# PLL.net
KiCad netlist of a schematic drawn in Altium Designer
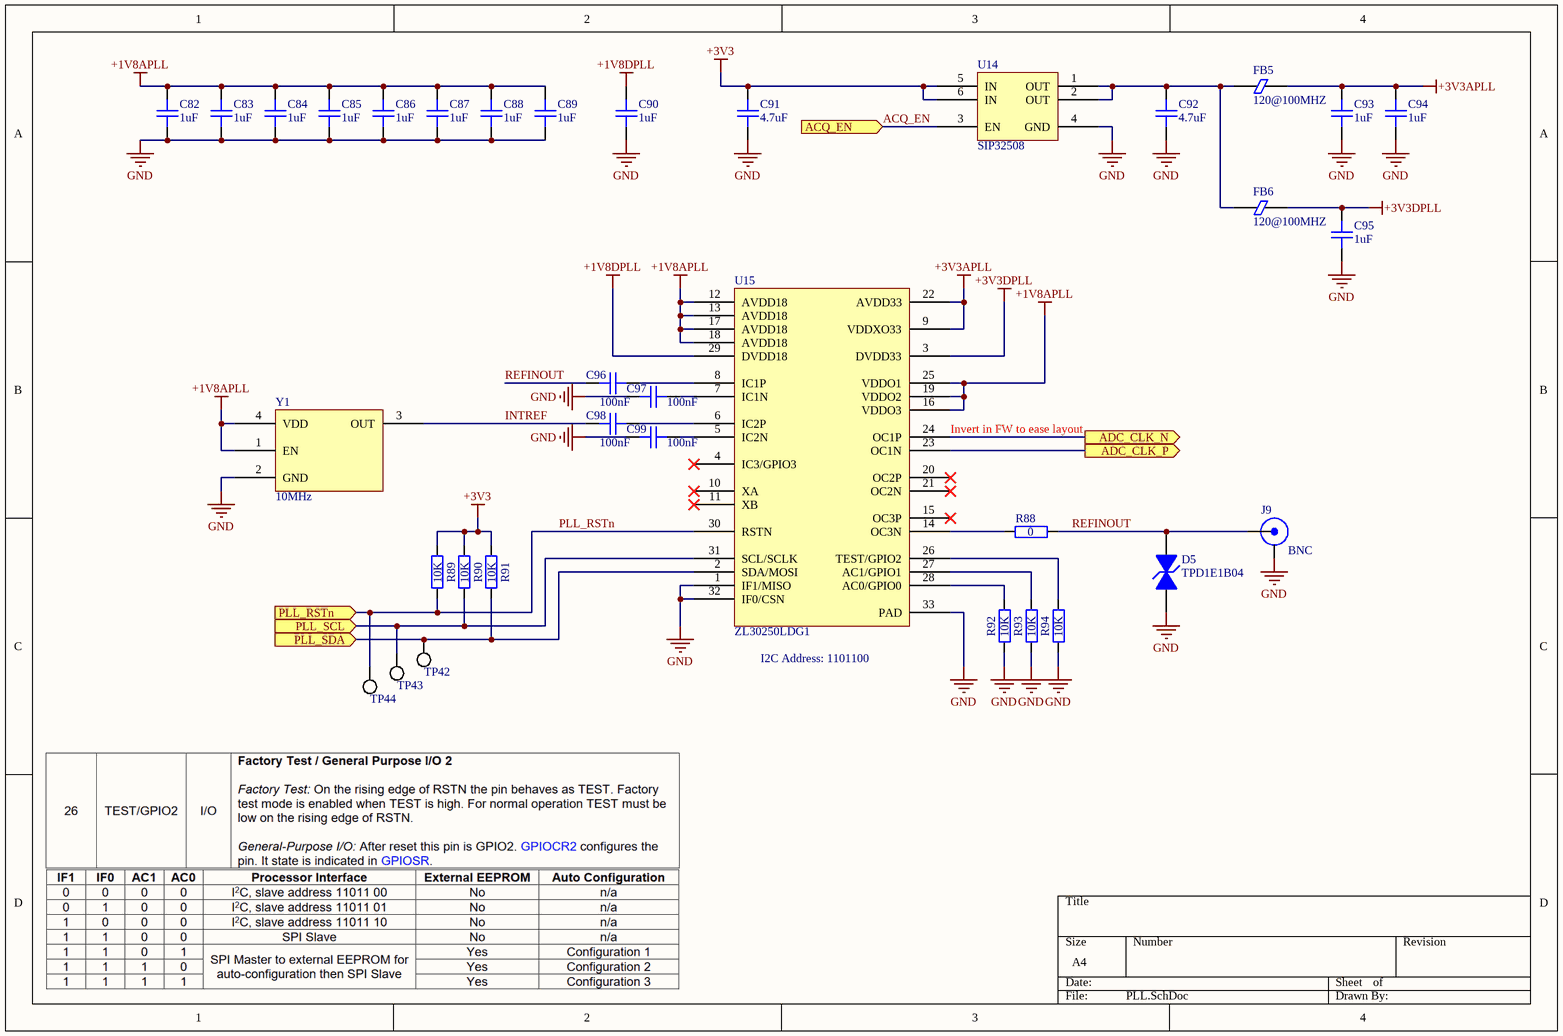
[diagram p0: PLL.SchDoc]

(export (version "E")
  (design (tool "Eeschema 10.0.6"))
  (components
    (comp (ref "C82")
      (value "1uF")
      (footprint "GEN_C_0402")
      (libsource (lib "DSO") (part "CAP 1uF 25V X5R 0402"))
    )
    (comp (ref "C83")
      (value "1uF")
      (footprint "GEN_C_0402")
      (libsource (lib "DSO") (part "CAP 1uF 25V X5R 0402"))
    )
    (comp (ref "C84")
      (value "1uF")
      (footprint "GEN_C_0402")
      (libsource (lib "DSO") (part "CAP 1uF 25V X5R 0402"))
    )
    (comp (ref "C85")
      (value "1uF")
      (footprint "GEN_C_0402")
      (libsource (lib "DSO") (part "CAP 1uF 25V X5R 0402"))
    )
    (comp (ref "C86")
      (value "1uF")
      (footprint "GEN_C_0402")
      (libsource (lib "DSO") (part "CAP 1uF 25V X5R 0402"))
    )
    (comp (ref "C87")
      (value "1uF")
      (footprint "GEN_C_0402")
      (libsource (lib "DSO") (part "CAP 1uF 25V X5R 0402"))
    )
    (comp (ref "C88")
      (value "1uF")
      (footprint "GEN_C_0402")
      (libsource (lib "DSO") (part "CAP 1uF 25V X5R 0402"))
    )
    (comp (ref "C89")
      (value "1uF")
      (footprint "GEN_C_0402")
      (libsource (lib "DSO") (part "CAP 1uF 25V X5R 0402"))
    )
    (comp (ref "C90")
      (value "1uF")
      (footprint "GEN_C_0402")
      (libsource (lib "DSO") (part "CAP 1uF 25V X5R 0402"))
    )
    (comp (ref "C91")
      (value "4.7uF")
      (footprint "GEN_C_0402")
      (libsource (lib "DSO") (part "CAP 4.7uF 6.3V X5R 0402"))
    )
    (comp (ref "C92")
      (value "4.7uF")
      (footprint "GEN_C_0402")
      (libsource (lib "DSO") (part "CAP 4.7uF 6.3V X5R 0402"))
    )
    (comp (ref "C93")
      (value "1uF")
      (footprint "GEN_C_0402")
      (libsource (lib "DSO") (part "CAP 1uF 25V X5R 0402"))
    )
    (comp (ref "C94")
      (value "1uF")
      (footprint "GEN_C_0402")
      (libsource (lib "DSO") (part "CAP 1uF 25V X5R 0402"))
    )
    (comp (ref "C95")
      (value "1uF")
      (footprint "GEN_C_0402")
      (libsource (lib "DSO") (part "CAP 1uF 25V X5R 0402"))
    )
    (comp (ref "C96")
      (value "100nF")
      (footprint "GEN_C_0402")
      (libsource (lib "DSO") (part "CAP 100nF 16V X7R 0402"))
    )
    (comp (ref "C97")
      (value "100nF")
      (footprint "GEN_C_0402")
      (libsource (lib "DSO") (part "CAP 100nF 16V X7R 0402"))
    )
    (comp (ref "C98")
      (value "100nF")
      (footprint "GEN_C_0402")
      (libsource (lib "DSO") (part "CAP 100nF 16V X7R 0402"))
    )
    (comp (ref "C99")
      (value "100nF")
      (footprint "GEN_C_0402")
      (libsource (lib "DSO") (part "CAP 100nF 16V X7R 0402"))
    )
    (comp (ref "D5")
      (value "TPD1E1B04")
      (footprint "TI_X1SON_DPY0002A")
      (libsource (lib "DSO") (part "TVS TPD1E1B04"))
    )
    (comp (ref "FB5")
      (value "120@100MHZ")
      (footprint "GEN_R_0402")
      (libsource (lib "DSO") (part "FERRITE BEAD 120 OHM 0402"))
    )
    (comp (ref "FB6")
      (value "120@100MHZ")
      (footprint "GEN_R_0402")
      (libsource (lib "DSO") (part "FERRITE BEAD 120 OHM 0402"))
    )
    (comp (ref "J9") (value "BNC") (footprint "MOL_0731000105") (libsource (lib "DSO") (part "BNC JACK R/A")))
    (comp (ref "R88")
      (value "0")
      (footprint "GEN_R_0402")
      (libsource (lib "DSO") (part "RES 0 OHM 1/16W 0402"))
    )
    (comp (ref "R89")
      (value "10K")
      (footprint "GEN_R_0402")
      (fields (field (name "TOLERANCE") "1%"))
      (libsource (lib "DSO") (part "RES 10K OHM 1% 1/10W 0402"))
    )
    (comp (ref "R90")
      (value "10K")
      (footprint "GEN_R_0402")
      (fields (field (name "TOLERANCE") "1%"))
      (libsource (lib "DSO") (part "RES 10K OHM 1% 1/10W 0402"))
    )
    (comp (ref "R91")
      (value "10K")
      (footprint "GEN_R_0402")
      (fields (field (name "TOLERANCE") "1%"))
      (libsource (lib "DSO") (part "RES 10K OHM 1% 1/10W 0402"))
    )
    (comp (ref "R92")
      (value "10K")
      (footprint "GEN_R_0402")
      (fields (field (name "TOLERANCE") "1%"))
      (libsource (lib "") (part "RES 10K OHM 1% 1/10W 0402_1"))
    )
    (comp (ref "R93")
      (value "10K")
      (footprint "GEN_R_0402")
      (fields (field (name "TOLERANCE") "1%"))
      (libsource (lib "") (part "RES 10K OHM 1% 1/10W 0402_1"))
    )
    (comp (ref "R94")
      (value "10K")
      (footprint "GEN_R_0402")
      (fields (field (name "TOLERANCE") "1%"))
      (libsource (lib "") (part "RES 10K OHM 1% 1/10W 0402_1"))
    )
    (comp (ref "TP42") (value "PCB") (footprint "GEN_TP_PCB") (libsource (lib "DSO") (part "TP PCB 1mm")))
    (comp (ref "TP43") (value "PCB") (footprint "GEN_TP_PCB") (libsource (lib "DSO") (part "TP PCB 1mm")))
    (comp (ref "TP44") (value "PCB") (footprint "GEN_TP_PCB") (libsource (lib "DSO") (part "TP PCB 1mm")))
    (comp (ref "U14")
      (value "SIP32508")
      (footprint "VISH_TSOT6")
      (libsource (lib "DSO") (part "IC SWITCH LOAD SIP32508"))
    )
    (comp (ref "U15")
      (value "ZL30250LDG1")
      (footprint "MC_QFN32_ZL30250")
      (libsource (lib "DSO") (part "IC CLK GEN ZL30250LDG1"))
    )
    (comp (ref "Y1")
      (value "10MHz")
      (footprint "ECS_TXO-3225")
      (libsource (lib "DSO") (part "OSC 10MHz ECS-TXO-3225MV"))
    )
  )
  (nets
    (net (code "1") (name "+1V8APLL") (class "Default")
      (node (ref "C82") (pin "1") (pinfunction "1_1") (pintype "passive"))
      (node (ref "C83") (pin "1") (pinfunction "1_1") (pintype "passive"))
      (node (ref "C84") (pin "1") (pinfunction "1_1") (pintype "passive"))
      (node (ref "C85") (pin "1") (pinfunction "1_1") (pintype "passive"))
      (node (ref "C86") (pin "1") (pinfunction "1_1") (pintype "passive"))
      (node (ref "C87") (pin "1") (pinfunction "1_1") (pintype "passive"))
      (node (ref "C88") (pin "1") (pinfunction "1_1") (pintype "passive"))
      (node (ref "C89") (pin "1") (pinfunction "1_1") (pintype "passive"))
      (node (ref "U15") (pin "12") (pinfunction "AVDD18_12") (pintype "passive"))
      (node (ref "U15") (pin "13") (pinfunction "AVDD18_13") (pintype "passive"))
      (node (ref "U15") (pin "16") (pinfunction "VDDO3_16") (pintype "passive"))
      (node (ref "U15") (pin "17") (pinfunction "AVDD18_17") (pintype "passive"))
      (node (ref "U15") (pin "18") (pinfunction "AVDD18_18") (pintype "passive"))
      (node (ref "U15") (pin "19") (pinfunction "VDDO2_19") (pintype "passive"))
      (node (ref "U15") (pin "25") (pinfunction "VDDO1_25") (pintype "passive"))
      (node (ref "Y1") (pin "1") (pinfunction "EN_1") (pintype "passive"))
      (node (ref "Y1") (pin "4") (pinfunction "VDD_4") (pintype "power_in"))
    )
    (net (code "2") (name "+1V8DPLL") (class "Default")
      (node (ref "C90") (pin "1") (pinfunction "1_1") (pintype "passive"))
      (node (ref "U15") (pin "29") (pinfunction "DVDD18_29") (pintype "passive"))
    )
    (net (code "3") (name "+3V3") (class "Default")
      (node (ref "C91") (pin "2") (pinfunction "2_2") (pintype "passive"))
      (node (ref "R89") (pin "2") (pinfunction "2_2") (pintype "passive"))
      (node (ref "R90") (pin "2") (pinfunction "2_2") (pintype "passive"))
      (node (ref "R91") (pin "2") (pinfunction "2_2") (pintype "passive"))
      (node (ref "U14") (pin "5") (pinfunction "IN_5") (pintype "passive"))
      (node (ref "U14") (pin "6") (pinfunction "IN_6") (pintype "passive"))
    )
    (net (code "4") (name "+3V3APLL") (class "Default")
      (node (ref "C93") (pin "1") (pinfunction "1_1") (pintype "passive"))
      (node (ref "C94") (pin "1") (pinfunction "1_1") (pintype "passive"))
      (node (ref "FB5") (pin "2") (pinfunction "2_2") (pintype "passive"))
      (node (ref "U15") (pin "22") (pinfunction "AVDD33_22") (pintype "passive"))
      (node (ref "U15") (pin "9") (pinfunction "VDDXO33_9") (pintype "passive"))
    )
    (net (code "5") (name "+3V3DPLL") (class "Default")
      (node (ref "C95") (pin "1") (pinfunction "1_1") (pintype "passive"))
      (node (ref "FB6") (pin "2") (pinfunction "2_2") (pintype "passive"))
      (node (ref "U15") (pin "3") (pinfunction "DVDD33_3") (pintype "passive"))
    )
    (net (code "6") (name "/ACQ_EN") (class "Default")
      (node (ref "U14") (pin "3") (pinfunction "EN_3") (pintype "passive"))
    )
    (net (code "7") (name "/ADC_CLK_N") (class "Default")
      (node (ref "U15") (pin "24") (pinfunction "OC1P_24") (pintype "passive"))
    )
    (net (code "8") (name "/ADC_CLK_P") (class "Default")
      (node (ref "U15") (pin "23") (pinfunction "OC1N_23") (pintype "passive"))
    )
    (net (code "9") (name "/INTREF") (class "Default")
      (node (ref "C98") (pin "2") (pinfunction "2_2") (pintype "passive"))
      (node (ref "Y1") (pin "3") (pinfunction "OUT_3") (pintype "passive"))
    )
    (net (code "10") (name "/PLL_RSTn") (class "Default")
      (node (ref "R89") (pin "1") (pinfunction "1_1") (pintype "passive"))
      (node (ref "TP44") (pin "1") (pinfunction "1_1") (pintype "passive"))
      (node (ref "U15") (pin "30") (pinfunction "RSTN_30") (pintype "passive"))
    )
    (net (code "11") (name "/PLL_SCL") (class "Default")
      (node (ref "R90") (pin "1") (pinfunction "1_1") (pintype "passive"))
      (node (ref "TP43") (pin "1") (pinfunction "1_1") (pintype "passive"))
      (node (ref "U15") (pin "31") (pinfunction "SCL/SCLK_31") (pintype "passive"))
    )
    (net (code "12") (name "/PLL_SDA") (class "Default")
      (node (ref "R91") (pin "1") (pinfunction "1_1") (pintype "passive"))
      (node (ref "TP42") (pin "1") (pinfunction "1_1") (pintype "passive"))
      (node (ref "U15") (pin "2") (pinfunction "SDA/MOSI_2") (pintype "passive"))
    )
    (net (code "13") (name "/REFINOUT") (class "Default")
      (node (ref "C96") (pin "2") (pinfunction "2_2") (pintype "passive"))
      (node (ref "D5") (pin "1") (pinfunction "K_1") (pintype "passive"))
      (node (ref "J9") (pin "1") (pinfunction "Signal_1") (pintype "passive"))
      (node (ref "R88") (pin "2") (pinfunction "2_2") (pintype "passive"))
    )
    (net (code "14") (name "GND") (class "Default")
      (node (ref "C82") (pin "2") (pinfunction "2_2") (pintype "passive"))
      (node (ref "C83") (pin "2") (pinfunction "2_2") (pintype "passive"))
      (node (ref "C84") (pin "2") (pinfunction "2_2") (pintype "passive"))
      (node (ref "C85") (pin "2") (pinfunction "2_2") (pintype "passive"))
      (node (ref "C86") (pin "2") (pinfunction "2_2") (pintype "passive"))
      (node (ref "C87") (pin "2") (pinfunction "2_2") (pintype "passive"))
      (node (ref "C88") (pin "2") (pinfunction "2_2") (pintype "passive"))
      (node (ref "C89") (pin "2") (pinfunction "2_2") (pintype "passive"))
      (node (ref "C90") (pin "2") (pinfunction "2_2") (pintype "passive"))
      (node (ref "C91") (pin "1") (pinfunction "1_1") (pintype "passive"))
      (node (ref "C92") (pin "1") (pinfunction "1_1") (pintype "passive"))
      (node (ref "C93") (pin "2") (pinfunction "2_2") (pintype "passive"))
      (node (ref "C94") (pin "2") (pinfunction "2_2") (pintype "passive"))
      (node (ref "C95") (pin "2") (pinfunction "2_2") (pintype "passive"))
      (node (ref "C97") (pin "2") (pinfunction "2_2") (pintype "passive"))
      (node (ref "C99") (pin "2") (pinfunction "2_2") (pintype "passive"))
      (node (ref "D5") (pin "2") (pinfunction "A_2") (pintype "passive"))
      (node (ref "J9") (pin "2") (pinfunction "SHIELD_2") (pintype "passive"))
      (node (ref "R92") (pin "1") (pinfunction "1_1") (pintype "passive"))
      (node (ref "R93") (pin "1") (pinfunction "1_1") (pintype "passive"))
      (node (ref "R94") (pin "1") (pinfunction "1_1") (pintype "passive"))
      (node (ref "U14") (pin "4") (pinfunction "GND_4") (pintype "passive"))
      (node (ref "U15") (pin "1") (pinfunction "IF1/MISO_1") (pintype "passive"))
      (node (ref "U15") (pin "32") (pinfunction "IF0/CSN_32") (pintype "passive"))
      (node (ref "U15") (pin "33") (pinfunction "PAD_33") (pintype "passive"))
      (node (ref "Y1") (pin "2") (pinfunction "GND_2") (pintype "power_in"))
    )
    (net (code "15") (name "Net-(C92-Pad2)") (class "Default")
      (node (ref "C92") (pin "2") (pinfunction "2_2") (pintype "passive"))
      (node (ref "FB5") (pin "1") (pinfunction "1_1") (pintype "passive"))
      (node (ref "FB6") (pin "1") (pinfunction "1_1") (pintype "passive"))
      (node (ref "U14") (pin "1") (pinfunction "OUT_1") (pintype "passive"))
      (node (ref "U14") (pin "2") (pinfunction "OUT_2") (pintype "passive"))
    )
    (net (code "16") (name "Net-(U15-AC0{slash}GPIO0)") (class "Default")
      (node (ref "R92") (pin "2") (pinfunction "2_2") (pintype "passive"))
      (node (ref "U15") (pin "28") (pinfunction "AC0/GPIO0_28") (pintype "passive"))
    )
    (net (code "17") (name "Net-(U15-AC1{slash}GPIO1)") (class "Default")
      (node (ref "R93") (pin "2") (pinfunction "2_2") (pintype "passive"))
      (node (ref "U15") (pin "27") (pinfunction "AC1/GPIO1_27") (pintype "passive"))
    )
    (net (code "18") (name "Net-(U15-IC1N)") (class "Default")
      (node (ref "C97") (pin "1") (pinfunction "1_1") (pintype "passive"))
      (node (ref "U15") (pin "7") (pinfunction "IC1N_7") (pintype "passive"))
    )
    (net (code "19") (name "Net-(U15-IC1P)") (class "Default")
      (node (ref "C96") (pin "1") (pinfunction "1_1") (pintype "passive"))
      (node (ref "U15") (pin "8") (pinfunction "IC1P_8") (pintype "passive"))
    )
    (net (code "20") (name "Net-(U15-IC2N)") (class "Default")
      (node (ref "C99") (pin "1") (pinfunction "1_1") (pintype "passive"))
      (node (ref "U15") (pin "5") (pinfunction "IC2N_5") (pintype "passive"))
    )
    (net (code "21") (name "Net-(U15-IC2P)") (class "Default")
      (node (ref "C98") (pin "1") (pinfunction "1_1") (pintype "passive"))
      (node (ref "U15") (pin "6") (pinfunction "IC2P_6") (pintype "passive"))
    )
    (net (code "22") (name "Net-(U15-OC3N)") (class "Default")
      (node (ref "R88") (pin "1") (pinfunction "1_1") (pintype "passive"))
      (node (ref "U15") (pin "14") (pinfunction "OC3N_14") (pintype "passive"))
    )
    (net (code "23") (name "Net-(U15-TEST{slash}GPIO2)") (class "Default")
      (node (ref "R94") (pin "2") (pinfunction "2_2") (pintype "passive"))
      (node (ref "U15") (pin "26") (pinfunction "TEST/GPIO2_26") (pintype "passive"))
    )
    (net (code "24") (name "unconnected-(U15-IC3{slash}GPIO3-Pad4)") (class "Default")
      (node (ref "U15") (pin "4") (pinfunction "IC3/GPIO3_4") (pintype "passive+no_connect"))
    )
    (net (code "25") (name "unconnected-(U15-OC2N-Pad21)") (class "Default")
      (node (ref "U15") (pin "21") (pinfunction "OC2N_21") (pintype "passive+no_connect"))
    )
    (net (code "26") (name "unconnected-(U15-OC2P-Pad20)") (class "Default")
      (node (ref "U15") (pin "20") (pinfunction "OC2P_20") (pintype "passive+no_connect"))
    )
    (net (code "27") (name "unconnected-(U15-OC3P-Pad15)") (class "Default")
      (node (ref "U15") (pin "15") (pinfunction "OC3P_15") (pintype "passive+no_connect"))
    )
    (net (code "28") (name "unconnected-(U15-XA-Pad10)") (class "Default")
      (node (ref "U15") (pin "10") (pinfunction "XA_10") (pintype "passive+no_connect"))
    )
    (net (code "29") (name "unconnected-(U15-XB-Pad11)") (class "Default")
      (node (ref "U15") (pin "11") (pinfunction "XB_11") (pintype "passive+no_connect"))
    )
  )
)
